# radioslave.net
KiCad netlist of a schematic drawn in Altium Designer
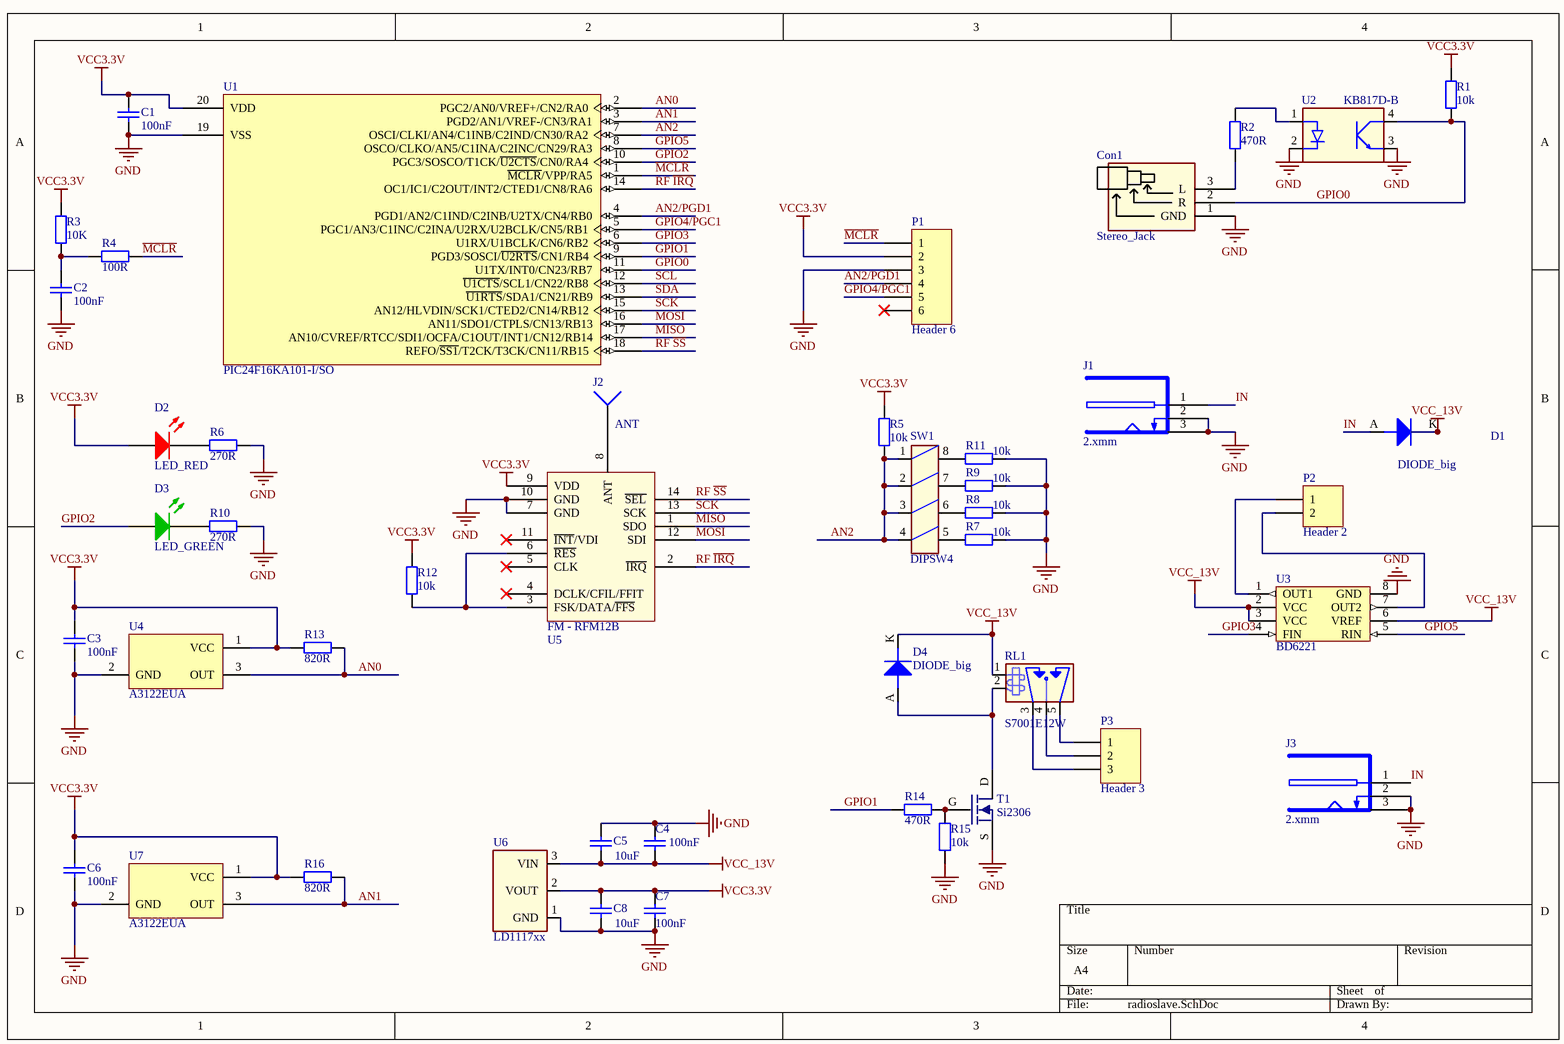
[diagram p0: radioslave.SchDoc]

(export (version "E")
  (design (tool "Eeschema 10.0.6"))
  (components
    (comp (ref "C1")
      (value "100nF")
      (footprint "FP_0805_CAP_060")
      (description "Capacitor")
      (fields (field (name "PUBLISHER") "Altium Limited"))
      (libsource (lib "Miscellaneous Devices") (part "Cap"))
    )
    (comp (ref "C2")
      (value "100nF")
      (footprint "FP_0805_CAP_060")
      (description "Capacitor")
      (fields (field (name "PUBLISHER") "Altium Limited"))
      (libsource (lib "Miscellaneous Devices") (part "Cap"))
    )
    (comp (ref "C3")
      (value "100nF")
      (footprint "FP_0805_CAP_060")
      (description "Capacitor")
      (fields (field (name "PUBLISHER") "Altium Limited"))
      (libsource (lib "Miscellaneous Devices") (part "Cap"))
    )
    (comp (ref "C4")
      (value "100nF")
      (footprint "FP_0603_CAP_080")
      (description "Capacitor")
      (fields (field (name "PUBLISHER") "Altium Limited"))
      (libsource (lib "Miscellaneous Devices") (part "Cap"))
    )
    (comp (ref "C5")
      (value "10uF")
      (footprint "FP_1206_CAP_085")
      (description "Capacitor")
      (fields (field (name "PUBLISHER") "Altium Limited"))
      (libsource (lib "Miscellaneous Devices") (part "Cap"))
    )
    (comp (ref "C6")
      (value "100nF")
      (footprint "FP_0805_CAP_060")
      (description "Capacitor")
      (fields (field (name "PUBLISHER") "Altium Limited"))
      (libsource (lib "Miscellaneous Devices") (part "Cap"))
    )
    (comp (ref "C7")
      (value "100nF")
      (footprint "FP_0603_CAP_080")
      (description "Capacitor")
      (fields (field (name "PUBLISHER") "Altium Limited"))
      (libsource (lib "Miscellaneous Devices") (part "Cap"))
    )
    (comp (ref "C8")
      (value "10uF")
      (footprint "FP_1206_CAP_085")
      (description "Capacitor")
      (fields (field (name "PUBLISHER") "Altium Limited"))
      (libsource (lib "Miscellaneous Devices") (part "Cap"))
    )
    (comp (ref "Con1")
      (value "Stereo_Jack")
      (footprint "STEREO_JACK")
      (libsource (lib "Connector") (part "Stereo_Jack"))
    )
    (comp (ref "D1")
      (value "DIODE_big")
      (footprint "FP_SMA DO214AC")
      (libsource (lib "Diode") (part "DIODE_big"))
    )
    (comp (ref "D2")
      (value "LED_RED")
      (footprint "FP_0805_LED_RED")
      (description "Typical LED")
      (libsource (lib "Led_optical") (part "LED_R"))
    )
    (comp (ref "D3")
      (value "LED_GREEN")
      (footprint "FP_0805_LED_RED")
      (description "Typical LED")
      (libsource (lib "Led_optical") (part "LED_G"))
    )
    (comp (ref "D4")
      (value "DIODE_big")
      (footprint "FP_SMA DO214AC")
      (libsource (lib "Diode") (part "DIODE_big"))
    )
    (comp (ref "J1")
      (value "2.xmm")
      (footprint "FP_DC_TAP_ANYA")
      (description "2.xmm DC HEBA25 TÁPFESZÜLTSÉG ALJZAT ZÁRT, NYÁKBA 90°")
      (libsource (lib "Connector") (part "DC_TAP_ANYA"))
    )
    (comp (ref "J2")
      (value "ANT")
      (footprint "PIN1")
      (description "Socket")
      (fields (field (name "PUBLISHER") "Altium Limited"))
      (libsource (lib "Miscellaneous Connectors") (part "Socket"))
    )
    (comp (ref "J3")
      (value "2.xmm")
      (footprint "FP_DC_TAP_ANYA")
      (description "2.xmm DC HEBA25 TÁPFESZÜLTSÉG ALJZAT ZÁRT, NYÁKBA 90°")
      (libsource (lib "Connector") (part "DC_TAP_ANYA"))
    )
    (comp (ref "P1")
      (value "Header 6")
      (footprint "HDR1X6")
      (description "Header, 6-Pin")
      (fields (field (name "PUBLISHER") "Altium Limited"))
      (libsource (lib "Miscellaneous Connectors") (part "Header 6"))
    )
    (comp (ref "P2")
      (value "Header 2")
      (footprint "HDR1X2")
      (description "Header, 2-Pin")
      (fields (field (name "PUBLISHER") "Altium Limited"))
      (libsource (lib "Miscellaneous Connectors") (part "Header 2"))
    )
    (comp (ref "P3")
      (value "Header 3")
      (footprint "SORKAPOCS 3 P RM3.81")
      (description "Header, 3-Pin")
      (fields (field (name "PUBLISHER") "Altium Limited"))
      (libsource (lib "Miscellaneous Connectors") (part "Header 3"))
    )
    (comp (ref "R1")
      (value "10k")
      (footprint "FP_0805_RES")
      (description "Resistor")
      (fields (field (name "PUBLISHER") "Altium Limited"))
      (libsource (lib "Miscellaneous Devices") (part "Res3"))
    )
    (comp (ref "R2")
      (value "470R")
      (footprint "FP_0805_RES")
      (description "Resistor")
      (fields (field (name "PUBLISHER") "Altium Limited"))
      (libsource (lib "Miscellaneous Devices") (part "Res3"))
    )
    (comp (ref "R3")
      (value "10K")
      (footprint "FP_0805_RES")
      (description "Resistor")
      (fields (field (name "PUBLISHER") "Altium Limited"))
      (libsource (lib "Miscellaneous Devices") (part "Res3"))
    )
    (comp (ref "R4")
      (value "100R")
      (footprint "FP_0805_RES")
      (description "Resistor")
      (fields (field (name "PUBLISHER") "Altium Limited"))
      (libsource (lib "") (part "Res3_1"))
    )
    (comp (ref "R5")
      (value "10k")
      (footprint "FP_0805_RES")
      (description "Resistor")
      (fields (field (name "PUBLISHER") "Altium Limited"))
      (libsource (lib "Miscellaneous Devices") (part "Res3"))
    )
    (comp (ref "R6")
      (value "270R")
      (footprint "FP_0805_RES")
      (description "Resistor")
      (fields (field (name "PUBLISHER") "Altium Limited"))
      (libsource (lib "") (part "Res3_1"))
    )
    (comp (ref "R7")
      (value "10k")
      (footprint "FP_0805_RES")
      (description "Resistor")
      (fields (field (name "PUBLISHER") "Altium Limited"))
      (libsource (lib "") (part "Res3_1"))
    )
    (comp (ref "R8")
      (value "10k")
      (footprint "FP_0805_RES")
      (description "Resistor")
      (fields (field (name "PUBLISHER") "Altium Limited"))
      (libsource (lib "") (part "Res3_1"))
    )
    (comp (ref "R9")
      (value "10k")
      (footprint "FP_0805_RES")
      (description "Resistor")
      (fields (field (name "PUBLISHER") "Altium Limited"))
      (libsource (lib "") (part "Res3_1"))
    )
    (comp (ref "R10")
      (value "270R")
      (footprint "FP_0805_RES")
      (description "Resistor")
      (fields (field (name "PUBLISHER") "Altium Limited"))
      (libsource (lib "") (part "Res3_1"))
    )
    (comp (ref "R11")
      (value "10k")
      (footprint "FP_0805_RES")
      (description "Resistor")
      (fields (field (name "PUBLISHER") "Altium Limited"))
      (libsource (lib "") (part "Res3_1"))
    )
    (comp (ref "R12")
      (value "10k")
      (footprint "FP_0805_RES")
      (description "Resistor")
      (fields (field (name "PUBLISHER") "Altium Limited"))
      (libsource (lib "") (part "Res3_2"))
    )
    (comp (ref "R13")
      (value "820R")
      (footprint "FP_0805_RES")
      (description "Resistor")
      (fields (field (name "PUBLISHER") "Altium Limited"))
      (libsource (lib "") (part "Res3_1"))
    )
    (comp (ref "R14")
      (value "470R")
      (footprint "FP_0805_RES")
      (description "Resistor")
      (fields (field (name "PUBLISHER") "Altium Limited"))
      (libsource (lib "") (part "Res3_1"))
    )
    (comp (ref "R15")
      (value "10k")
      (footprint "FP_0805_RES")
      (description "Resistor")
      (fields (field (name "PUBLISHER") "Altium Limited"))
      (libsource (lib "") (part "Res3_2"))
    )
    (comp (ref "R16")
      (value "820R")
      (footprint "FP_0805_RES")
      (description "Resistor")
      (fields (field (name "PUBLISHER") "Altium Limited"))
      (libsource (lib "") (part "Res3_1"))
    )
    (comp (ref "RL1")
      (value "S7001E12W")
      (footprint "RELAY_MORSE")
      (description "S7001E12W  12V morse 230AC/10A")
      (libsource (lib "Switch") (part "RELAY_MORSE"))
    )
    (comp (ref "SW1")
      (value "DIPSW4")
      (footprint "DIP switch 4 TH")
      (libsource (lib "Switch") (part "DIPSW4"))
    )
    (comp (ref "T1") (value "Si2306") (footprint "FET_SOT23") (libsource (lib "FET") (part "NMOS")))
    (comp (ref "U1")
      (value "PIC24F16KA101-I/SO")
      (footprint "SOIC-SO20_N")
      (fields (field (name "PUBLISHER") "Altium Limited"))
      (libsource (lib "Microchip Microcontroller 16-Bit PIC24F") (part "PIC24F16KA101-I/SO"))
    )
    (comp (ref "U2")
      (value "KB817D-B")
      (footprint "SOP-4L")
      (description "KB817D-B (KIN) SOP-4L OPTOCOUPLER TRANS-OUT 300-600% 5kV SOP-4L [84-00-48]")
      (libsource (lib "Led_optical") (part "KB817D-B"))
    )
    (comp (ref "U3")
      (value "BD6221")
      (footprint "Digital:DIGITAL_SOIC8")
      (description "H_bridge")
      (libsource (lib "Digital") (part "BD6221"))
    )
    (comp (ref "U4")
      (value "A3122EUA")
      (footprint "Allegro_hall sensor")
      (description "Hall-Effect Switch for High-Temperature Operation")
      (fields (field (name "PUBLISHER") "Altium Limited"))
      (libsource (lib "Sensor") (part "A3122EUA"))
    )
    (comp (ref "U5")
      (value "RFM12B")
      (footprint "RFM12B-S1")
      (description "FM Module")
      (libsource (lib "EtherIOv2") (part "RFM12B"))
    )
    (comp (ref "U6")
      (value "LD1117xx")
      (footprint "SUPPLY_SOT223")
      (description "LD1117xx 3,3V lin reg")
      (libsource (lib "Supply") (part "LD1117xx"))
    )
    (comp (ref "U7")
      (value "A3122EUA")
      (footprint "Allegro_hall sensor")
      (description "Hall-Effect Switch for High-Temperature Operation")
      (fields (field (name "PUBLISHER") "Altium Limited"))
      (libsource (lib "Sensor") (part "A3122EUA"))
    )
  )
  (nets
    (net (code "1") (name "/AN0") (class "Default")
      (node (ref "R13") (pin "1") (pinfunction "1_1") (pintype "passive"))
      (node (ref "U1") (pin "2") (pinfunction "PGC2/AN0/VREF+/CN2/RA0_2") (pintype "bidirectional"))
      (node (ref "U4") (pin "3") (pinfunction "OUT_3") (pintype "open_collector"))
    )
    (net (code "2") (name "/AN1") (class "Default")
      (node (ref "R16") (pin "1") (pinfunction "1_1") (pintype "passive"))
      (node (ref "U1") (pin "3") (pinfunction "PGD2/AN1/VREF-/CN3/RA1_3") (pintype "bidirectional"))
      (node (ref "U7") (pin "3") (pinfunction "OUT_3") (pintype "open_collector"))
    )
    (net (code "3") (name "/AN2") (class "Default")
      (node (ref "R5") (pin "2") (pinfunction "2_2") (pintype "passive"))
      (node (ref "SW1") (pin "1") (pinfunction "1_1") (pintype "passive"))
      (node (ref "SW1") (pin "2") (pinfunction "2_2") (pintype "passive"))
      (node (ref "SW1") (pin "3") (pinfunction "3_3") (pintype "passive"))
      (node (ref "SW1") (pin "4") (pinfunction "4_4") (pintype "passive"))
      (node (ref "U1") (pin "7") (pinfunction "OSCI/CLKI/AN4/C1INB/C2IND/CN30/RA2_7") (pintype "bidirectional"))
    )
    (net (code "4") (name "/AN2{slash}PGD1") (class "Default")
      (node (ref "P1") (pin "4") (pinfunction "4_4") (pintype "passive"))
      (node (ref "U1") (pin "4") (pinfunction "PGD1/AN2/C1IND/C2INB/U2TX/CN4/RB0_4") (pintype "bidirectional"))
    )
    (net (code "5") (name "/GPIO0") (class "Default")
      (node (ref "Con1") (pin "2") (pinfunction "R_2") (pintype "passive"))
      (node (ref "R1") (pin "2") (pinfunction "2_2") (pintype "passive"))
      (node (ref "U1") (pin "11") (pinfunction "U1TX/INT0/CN23/RB7_11") (pintype "bidirectional"))
      (node (ref "U2") (pin "4") (pinfunction "C_4") (pintype "passive"))
    )
    (net (code "6") (name "/GPIO1") (class "Default")
      (node (ref "R14") (pin "2") (pinfunction "2_2") (pintype "passive"))
      (node (ref "U1") (pin "9") (pinfunction "PGD3/SOSCI/~{U2RTS}/CN1/RB4_9") (pintype "bidirectional"))
    )
    (net (code "7") (name "/GPIO2") (class "Default")
      (node (ref "D3") (pin "A") (pinfunction "A_A") (pintype "passive"))
      (node (ref "U1") (pin "10") (pinfunction "PGC3/SOSCO/T1CK/~{U2CTS}/CN0/RA4_10") (pintype "bidirectional"))
    )
    (net (code "8") (name "/GPIO3") (class "Default")
      (node (ref "U1") (pin "6") (pinfunction "U1RX/U1BCLK/CN6/RB2_6") (pintype "bidirectional"))
      (node (ref "U3") (pin "4") (pinfunction "FIN_4") (pintype "input"))
    )
    (net (code "9") (name "/GPIO4{slash}PGC1") (class "Default")
      (node (ref "P1") (pin "5") (pinfunction "5_5") (pintype "passive"))
      (node (ref "U1") (pin "5") (pinfunction "PGC1/AN3/C1INC/C2INA/U2RX/U2BCLK/CN5/RB1_5") (pintype "bidirectional"))
    )
    (net (code "10") (name "/GPIO5") (class "Default")
      (node (ref "U1") (pin "8") (pinfunction "OSCO/CLKO/AN5/C1INA/C2INC/CN29/RA3_8") (pintype "bidirectional"))
      (node (ref "U3") (pin "5") (pinfunction "RIN_5") (pintype "input"))
    )
    (net (code "11") (name "/IN") (class "Default")
      (node (ref "D1") (pin "A") (pinfunction "A_A") (pintype "passive"))
      (node (ref "J1") (pin "1") (pinfunction "9V_1") (pintype "power_in"))
      (node (ref "J3") (pin "1") (pinfunction "9V_1") (pintype "power_in"))
    )
    (net (code "12") (name "/MISO") (class "Default")
      (node (ref "U1") (pin "17") (pinfunction "AN10/CVREF/RTCC/SDI1/OCFA/C1OUT/INT1/CN12/RB14_17") (pintype "bidirectional"))
      (node (ref "U5") (pin "1") (pinfunction "SDO_1") (pintype "passive"))
    )
    (net (code "13") (name "/MOSI") (class "Default")
      (node (ref "U1") (pin "16") (pinfunction "AN11/SDO1/CTPLS/CN13/RB13_16") (pintype "bidirectional"))
      (node (ref "U5") (pin "12") (pinfunction "SDI_12") (pintype "passive"))
    )
    (net (code "14") (name "/RF ~{IRQ}") (class "Default")
      (node (ref "U1") (pin "14") (pinfunction "OC1/IC1/C2OUT/INT2/CTED1/CN8/RA6_14") (pintype "bidirectional"))
      (node (ref "U5") (pin "2") (pinfunction "~{IRQ}_2") (pintype "passive"))
    )
    (net (code "15") (name "/RF ~{SS}") (class "Default")
      (node (ref "U1") (pin "18") (pinfunction "REFO/~{SS1}/T2CK/T3CK/CN11/RB15_18") (pintype "bidirectional"))
      (node (ref "U5") (pin "14") (pinfunction "~{SEL}_14") (pintype "passive"))
    )
    (net (code "16") (name "/SCK") (class "Default")
      (node (ref "U1") (pin "15") (pinfunction "AN12/HLVDIN/SCK1/CTED2/CN14/RB12_15") (pintype "bidirectional"))
      (node (ref "U5") (pin "13") (pinfunction "SCK_13") (pintype "passive"))
    )
    (net (code "17") (name "/SCL") (class "Default")
      (node (ref "U1") (pin "12") (pinfunction "~{U1CTS}/SCL1/CN22/RB8_12") (pintype "bidirectional"))
    )
    (net (code "18") (name "/SDA") (class "Default")
      (node (ref "U1") (pin "13") (pinfunction "~{U1RTS}/SDA1/CN21/RB9_13") (pintype "bidirectional"))
    )
    (net (code "19") (name "/~{MCLR}") (class "Default")
      (node (ref "P1") (pin "1") (pinfunction "1_1") (pintype "passive"))
      (node (ref "R4") (pin "1") (pinfunction "1_1") (pintype "passive"))
      (node (ref "U1") (pin "1") (pinfunction "~{MCLR}/VPP/RA5_1") (pintype "bidirectional"))
    )
    (net (code "20") (name "GND") (class "Default")
      (node (ref "C1") (pin "1") (pinfunction "1_1") (pintype "passive"))
      (node (ref "C2") (pin "1") (pinfunction "1_1") (pintype "passive"))
      (node (ref "C3") (pin "1") (pinfunction "1_1") (pintype "passive"))
      (node (ref "C4") (pin "1") (pinfunction "1_1") (pintype "passive"))
      (node (ref "C5") (pin "2") (pinfunction "2_2") (pintype "passive"))
      (node (ref "C6") (pin "1") (pinfunction "1_1") (pintype "passive"))
      (node (ref "C7") (pin "2") (pinfunction "2_2") (pintype "passive"))
      (node (ref "C8") (pin "1") (pinfunction "1_1") (pintype "passive"))
      (node (ref "Con1") (pin "1") (pinfunction "GND_1") (pintype "passive"))
      (node (ref "J1") (pin "2") (pinfunction "GND_2") (pintype "power_in"))
      (node (ref "J1") (pin "3") (pinfunction "GND_3") (pintype "power_in"))
      (node (ref "J3") (pin "2") (pinfunction "GND_2") (pintype "power_in"))
      (node (ref "J3") (pin "3") (pinfunction "GND_3") (pintype "power_in"))
      (node (ref "P1") (pin "3") (pinfunction "3_3") (pintype "passive"))
      (node (ref "R10") (pin "1") (pinfunction "1_1") (pintype "passive"))
      (node (ref "R11") (pin "1") (pinfunction "1_1") (pintype "passive"))
      (node (ref "R15") (pin "1") (pinfunction "1_1") (pintype "passive"))
      (node (ref "R6") (pin "1") (pinfunction "1_1") (pintype "passive"))
      (node (ref "R7") (pin "1") (pinfunction "1_1") (pintype "passive"))
      (node (ref "R8") (pin "1") (pinfunction "1_1") (pintype "passive"))
      (node (ref "R9") (pin "1") (pinfunction "1_1") (pintype "passive"))
      (node (ref "T1") (pin "S") (pinfunction "S_S") (pintype "passive"))
      (node (ref "U1") (pin "19") (pinfunction "VSS_19") (pintype "power_in"))
      (node (ref "U2") (pin "2") (pinfunction "K_2") (pintype "passive"))
      (node (ref "U2") (pin "3") (pinfunction "E_3") (pintype "passive"))
      (node (ref "U3") (pin "8") (pinfunction "GND_8") (pintype "passive"))
      (node (ref "U4") (pin "2") (pinfunction "GND_2") (pintype "power_in"))
      (node (ref "U5") (pin "10") (pinfunction "GND_10") (pintype "passive"))
      (node (ref "U5") (pin "7") (pinfunction "GND_7") (pintype "passive"))
      (node (ref "U6") (pin "1") (pinfunction "GND_1") (pintype "passive"))
      (node (ref "U7") (pin "2") (pinfunction "GND_2") (pintype "power_in"))
    )
    (net (code "21") (name "Net-(C2-Pad2)") (class "Default")
      (node (ref "C2") (pin "2") (pinfunction "2_2") (pintype "passive"))
      (node (ref "R3") (pin "2") (pinfunction "2_2") (pintype "passive"))
      (node (ref "R4") (pin "2") (pinfunction "2_2") (pintype "passive"))
    )
    (net (code "22") (name "Net-(Con1-L)") (class "Default")
      (node (ref "Con1") (pin "3") (pinfunction "L_3") (pintype "passive"))
      (node (ref "R2") (pin "2") (pinfunction "2_2") (pintype "passive"))
    )
    (net (code "23") (name "Net-(D2-PadK)") (class "Default")
      (node (ref "D2") (pin "K") (pinfunction "K_K") (pintype "passive"))
      (node (ref "R6") (pin "2") (pinfunction "2_2") (pintype "passive"))
    )
    (net (code "24") (name "Net-(D3-PadK)") (class "Default")
      (node (ref "D3") (pin "K") (pinfunction "K_K") (pintype "passive"))
      (node (ref "R10") (pin "2") (pinfunction "2_2") (pintype "passive"))
    )
    (net (code "25") (name "Net-(R7-Pad2)") (class "Default")
      (node (ref "R7") (pin "2") (pinfunction "2_2") (pintype "passive"))
      (node (ref "SW1") (pin "5") (pinfunction "5_5") (pintype "passive"))
    )
    (net (code "26") (name "Net-(R8-Pad2)") (class "Default")
      (node (ref "R8") (pin "2") (pinfunction "2_2") (pintype "passive"))
      (node (ref "SW1") (pin "6") (pinfunction "6_6") (pintype "passive"))
    )
    (net (code "27") (name "Net-(R9-Pad2)") (class "Default")
      (node (ref "R9") (pin "2") (pinfunction "2_2") (pintype "passive"))
      (node (ref "SW1") (pin "7") (pinfunction "7_7") (pintype "passive"))
    )
    (net (code "28") (name "Net-(R11-Pad2)") (class "Default")
      (node (ref "R11") (pin "2") (pinfunction "2_2") (pintype "passive"))
      (node (ref "SW1") (pin "8") (pinfunction "8_8") (pintype "passive"))
    )
    (net (code "29") (name "Net-(R14-Pad1)") (class "Default")
      (node (ref "R14") (pin "1") (pinfunction "1_1") (pintype "passive"))
      (node (ref "R15") (pin "2") (pinfunction "2_2") (pintype "passive"))
      (node (ref "T1") (pin "G") (pinfunction "G_G") (pintype "passive"))
    )
    (net (code "30") (name "Net-(RL1-COIL2+)") (class "Default")
      (node (ref "D4") (pin "A") (pinfunction "A_A") (pintype "passive"))
      (node (ref "RL1") (pin "2") (pinfunction "COIL2+_2") (pintype "passive"))
      (node (ref "T1") (pin "D") (pinfunction "D_D") (pintype "passive"))
    )
    (net (code "31") (name "Net-(RL1-COMMON)") (class "Default")
      (node (ref "P3") (pin "2") (pinfunction "2_2") (pintype "passive"))
      (node (ref "RL1") (pin "4") (pinfunction "COMMON_4") (pintype "passive"))
    )
    (net (code "32") (name "Net-(RL1-NC)") (class "Default")
      (node (ref "P3") (pin "3") (pinfunction "3_3") (pintype "passive"))
      (node (ref "RL1") (pin "3") (pinfunction "NC_3") (pintype "passive"))
    )
    (net (code "33") (name "Net-(RL1-NO)") (class "Default")
      (node (ref "P3") (pin "1") (pinfunction "1_1") (pintype "passive"))
      (node (ref "RL1") (pin "5") (pinfunction "NO_5") (pintype "passive"))
    )
    (net (code "34") (name "Net-(U2-A)") (class "Default")
      (node (ref "R2") (pin "1") (pinfunction "1_1") (pintype "passive"))
      (node (ref "U2") (pin "1") (pinfunction "A_1") (pintype "passive"))
    )
    (net (code "35") (name "Net-(U3-OUT1)") (class "Default")
      (node (ref "P2") (pin "1") (pinfunction "1_1") (pintype "passive"))
      (node (ref "U3") (pin "1") (pinfunction "OUT1_1") (pintype "output"))
    )
    (net (code "36") (name "Net-(U3-OUT2)") (class "Default")
      (node (ref "P2") (pin "2") (pinfunction "2_2") (pintype "passive"))
      (node (ref "U3") (pin "7") (pinfunction "OUT2_7") (pintype "output"))
    )
    (net (code "37") (name "Net-(U5-ANT)") (class "Default")
      (node (ref "J2") (pin "1") (pinfunction "1_1") (pintype "passive"))
      (node (ref "U5") (pin "8") (pinfunction "ANT_8") (pintype "passive"))
    )
    (net (code "38") (name "Net-(U5-FSK{slash}DATA{slash}~{FFS})") (class "Default")
      (node (ref "R12") (pin "1") (pinfunction "1_1") (pintype "passive"))
      (node (ref "U5") (pin "3") (pinfunction "FSK/DATA/~{FFS}_3") (pintype "passive"))
      (node (ref "U5") (pin "6") (pinfunction "~{RES}_6") (pintype "passive"))
    )
    (net (code "39") (name "VCC3.3V") (class "Default")
      (node (ref "C1") (pin "2") (pinfunction "2_2") (pintype "passive"))
      (node (ref "C3") (pin "2") (pinfunction "2_2") (pintype "passive"))
      (node (ref "C6") (pin "2") (pinfunction "2_2") (pintype "passive"))
      (node (ref "C7") (pin "1") (pinfunction "1_1") (pintype "passive"))
      (node (ref "C8") (pin "2") (pinfunction "2_2") (pintype "passive"))
      (node (ref "D2") (pin "A") (pinfunction "A_A") (pintype "passive"))
      (node (ref "P1") (pin "2") (pinfunction "2_2") (pintype "passive"))
      (node (ref "R1") (pin "1") (pinfunction "1_1") (pintype "passive"))
      (node (ref "R12") (pin "2") (pinfunction "2_2") (pintype "passive"))
      (node (ref "R13") (pin "2") (pinfunction "2_2") (pintype "passive"))
      (node (ref "R16") (pin "2") (pinfunction "2_2") (pintype "passive"))
      (node (ref "R3") (pin "1") (pinfunction "1_1") (pintype "passive"))
      (node (ref "R5") (pin "1") (pinfunction "1_1") (pintype "passive"))
      (node (ref "U1") (pin "20") (pinfunction "VDD_20") (pintype "power_in"))
      (node (ref "U4") (pin "1") (pinfunction "VCC_1") (pintype "power_in"))
      (node (ref "U5") (pin "9") (pinfunction "VDD_9") (pintype "passive"))
      (node (ref "U6") (pin "2") (pinfunction "VOUT_2") (pintype "passive"))
      (node (ref "U7") (pin "1") (pinfunction "VCC_1") (pintype "power_in"))
    )
    (net (code "40") (name "VCC_13V") (class "Default")
      (node (ref "C4") (pin "2") (pinfunction "2_2") (pintype "passive"))
      (node (ref "C5") (pin "1") (pinfunction "1_1") (pintype "passive"))
      (node (ref "D1") (pin "K") (pinfunction "K_K") (pintype "passive"))
      (node (ref "D4") (pin "K") (pinfunction "K_K") (pintype "passive"))
      (node (ref "RL1") (pin "1") (pinfunction "COIL1-_1") (pintype "passive"))
      (node (ref "U3") (pin "2") (pinfunction "VCC_2") (pintype "power_in"))
      (node (ref "U3") (pin "3") (pinfunction "VCC_3") (pintype "power_in"))
      (node (ref "U3") (pin "6") (pinfunction "VREF_6") (pintype "passive"))
      (node (ref "U6") (pin "3") (pinfunction "VIN_3") (pintype "passive"))
    )
    (net (code "41") (name "unconnected-(P1-Pad6)") (class "Default")
      (node (ref "P1") (pin "6") (pinfunction "6_6") (pintype "passive+no_connect"))
    )
    (net (code "42") (name "unconnected-(U5-CLK-Pad5)") (class "Default")
      (node (ref "U5") (pin "5") (pinfunction "CLK_5") (pintype "passive+no_connect"))
    )
    (net (code "43") (name "unconnected-(U5-DCLK{slash}CFIL{slash}FFIT-Pad4)") (class "Default")
      (node (ref "U5") (pin "4") (pinfunction "DCLK/CFIL/FFIT_4") (pintype "passive+no_connect"))
    )
    (net (code "44") (name "unconnected-(U5-~{INT}{slash}VDI-Pad11)") (class "Default")
      (node (ref "U5") (pin "11") (pinfunction "~{INT}/VDI_11") (pintype "passive+no_connect"))
    )
  )
)
